# 03-USER_IO_STATUS.net
KiCad netlist of a schematic drawn in Altium Designer
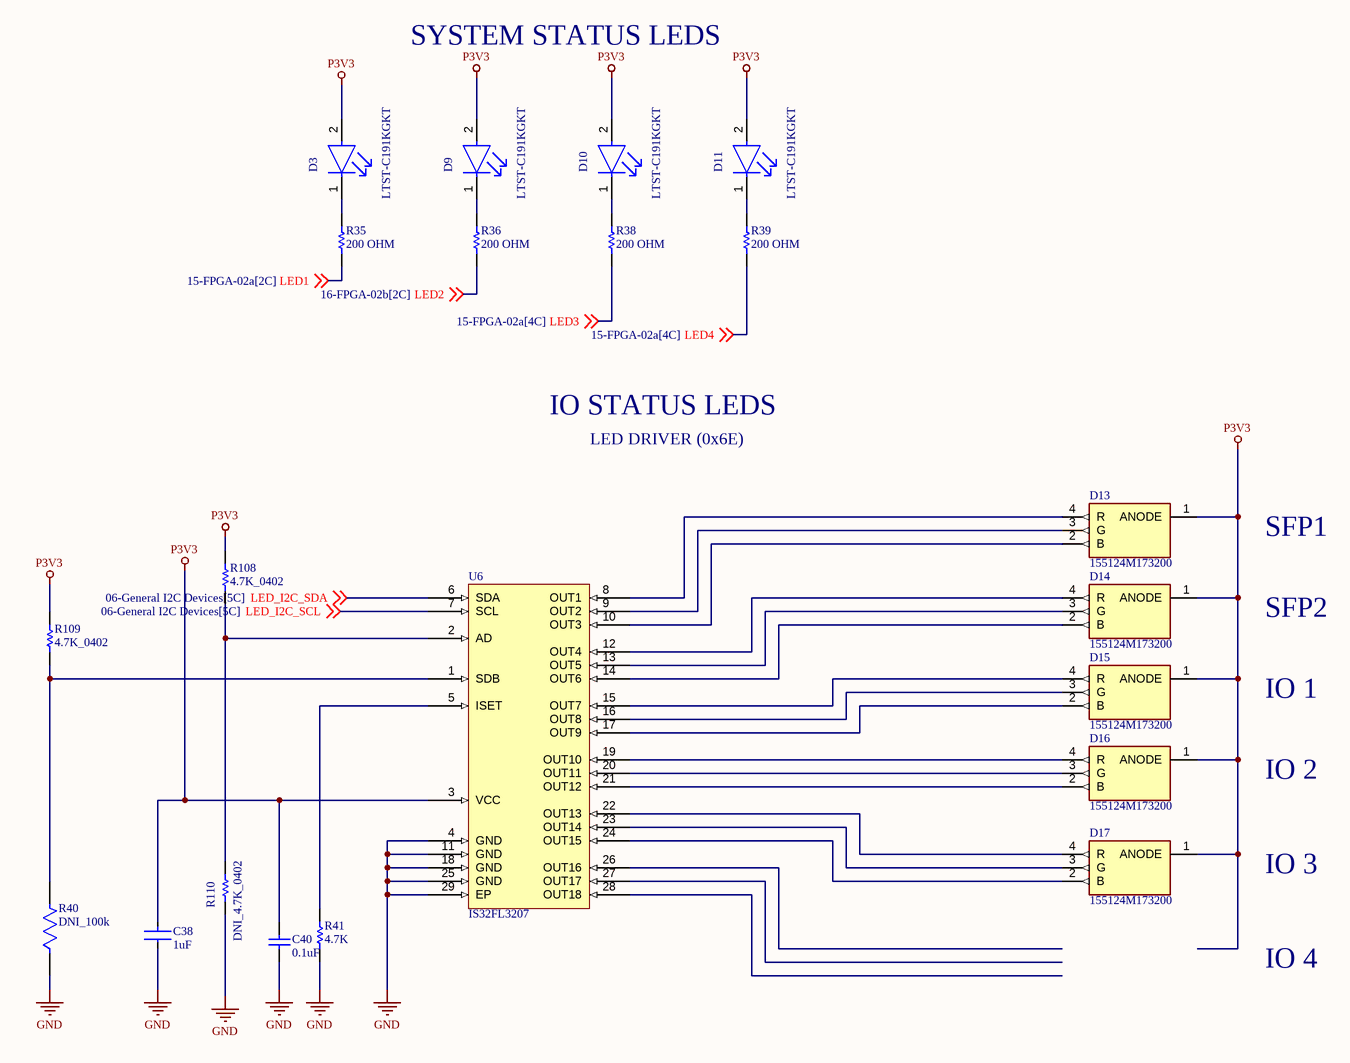
[diagram p0: 03-USER_IO_STATUS.SchDoc]

(export (version "E")
  (design (tool "Eeschema 10.0.6"))
  (components
    (comp (ref "C38")
      (value "1uF")
      (footprint "FP-C0603C105K3PACTU-MFG")
      (description "CAP CER 1UF 25V X5R 0603")
      (fields (field (name "VOLTAGE") "25V") (field (name "TOLERANCE") "10%"))
      (libsource (lib "Altium Content Vault") (part "e9c51b7dd13d4faca003ae77663ab08"))
    )
    (comp (ref "C40")
      (value "0.1uF")
      (footprint "CAPC1608X87X45ML20T05")
      (description "C0603X104K5RACAUTO")
      (fields (field (name "MANUFACTURER") "Kemet"))
      (libsource (lib "Altium Content Vault") (part "CAP"))
    )
    (comp (ref "D3")
      (value "LTST-C191KGKT")
      (footprint "FP-LTST-C191KGKT-MFG")
      (description "LED GREEN CLEAR SMD")
      (libsource (lib "Altium Content Vault") (part "8706943c75ba83719d021d2fdc84c58"))
    )
    (comp (ref "D9")
      (value "LTST-C191KGKT")
      (footprint "FP-LTST-C191KGKT-MFG")
      (description "LED GREEN CLEAR SMD")
      (libsource (lib "Altium Content Vault") (part "8706943c75ba83719d021d2fdc84c58"))
    )
    (comp (ref "D10")
      (value "LTST-C191KGKT")
      (footprint "FP-LTST-C191KGKT-MFG")
      (description "LED GREEN CLEAR SMD")
      (libsource (lib "Altium Content Vault") (part "8706943c75ba83719d021d2fdc84c58"))
    )
    (comp (ref "D11")
      (value "LTST-C191KGKT")
      (footprint "FP-LTST-C191KGKT-MFG")
      (description "LED GREEN CLEAR SMD")
      (libsource (lib "Altium Content Vault") (part "8706943c75ba83719d021d2fdc84c58"))
    )
    (comp (ref "D13")
      (value "155124M173200")
      (footprint "SamacSys:155124M173200")
      (description "LED (Multiple)")
      (fields (field (name "MOUSER PART NUMBER") "710-155124M173200"))
      (libsource (lib "SamacSys") (part "155124M173200"))
    )
    (comp (ref "D14")
      (value "155124M173200")
      (footprint "SamacSys:155124M173200")
      (description "LED (Multiple)")
      (fields (field (name "MOUSER PART NUMBER") "710-155124M173200"))
      (libsource (lib "SamacSys") (part "155124M173200"))
    )
    (comp (ref "D15")
      (value "155124M173200")
      (footprint "SamacSys:155124M173200")
      (description "LED (Multiple)")
      (fields (field (name "MOUSER PART NUMBER") "710-155124M173200"))
      (libsource (lib "SamacSys") (part "155124M173200"))
    )
    (comp (ref "D16")
      (value "155124M173200")
      (footprint "SamacSys:155124M173200")
      (description "LED (Multiple)")
      (fields (field (name "MOUSER PART NUMBER") "710-155124M173200"))
      (libsource (lib "SamacSys") (part "155124M173200"))
    )
    (comp (ref "D17")
      (value "155124M173200")
      (footprint "SamacSys:155124M173200")
      (description "LED (Multiple)")
      (fields (field (name "MOUSER PART NUMBER") "710-155124M173200"))
      (libsource (lib "SamacSys") (part "155124M173200"))
    )
    (comp (ref "R35")
      (value "200 OHM")
      (footprint "RESC1608X55X30NL15T15")
      (description "ERJ-3EKF2000V")
      (fields (field (name "MANUFACTURER") "Panasonic"))
      (libsource (lib "Altium Content Vault") (part "RES"))
    )
    (comp (ref "R36")
      (value "200 OHM")
      (footprint "RESC1608X55X30NL15T15")
      (description "ERJ-3EKF2000V")
      (fields (field (name "MANUFACTURER") "Panasonic"))
      (libsource (lib "Altium Content Vault") (part "RES"))
    )
    (comp (ref "R38")
      (value "200 OHM")
      (footprint "RESC1608X55X30NL15T15")
      (description "ERJ-3EKF2000V")
      (fields (field (name "MANUFACTURER") "Panasonic"))
      (libsource (lib "Altium Content Vault") (part "RES"))
    )
    (comp (ref "R39")
      (value "200 OHM")
      (footprint "RESC1608X55X30NL15T15")
      (description "ERJ-3EKF2000V")
      (fields (field (name "MANUFACTURER") "Panasonic"))
      (libsource (lib "Altium Content Vault") (part "RES"))
    )
    (comp (ref "R40")
      (value "DNI_100k")
      (footprint "FP-RC0603-0_55-MFG")
      (description "RES SMD 100K OHM 1% 1/10W 0603")
      (fields (field (name "TOLERANCE") "1%"))
      (libsource (lib "Altium Content Vault") (part "1029c3af85768c4190bb7ad29bc67b5"))
    )
    (comp (ref "R41")
      (value "4.7K")
      (footprint "RESC1608X55X30NL15T15")
      (fields (field (name "TOLERANCE") "5%"))
      (libsource (lib "Altium Content Vault") (part "RES-2"))
    )
    (comp (ref "R108")
      (value "4.7K_0402")
      (footprint "RESC1005X40X25LL05T05")
      (description "Chip Resistor, 4.7 KOhm, +/- 1%, 0.1 W, -55 to 155 degC, 0402 (1005 Metric), RoHS, Tape and Reel")
      (fields (field (name "TOLERANCE") "1%") (field (name "PARTNUMBER") "ERJ-2RKF4701X"))
      (libsource (lib "Altium Content Vault") (part "RES-2"))
    )
    (comp (ref "R109")
      (value "4.7K_0402")
      (footprint "RESC1005X40X25LL05T05")
      (description "Chip Resistor, 4.7 KOhm, +/- 1%, 0.1 W, -55 to 155 degC, 0402 (1005 Metric), RoHS, Tape and Reel")
      (fields (field (name "TOLERANCE") "1%") (field (name "PARTNUMBER") "ERJ-2RKF4701X"))
      (libsource (lib "Altium Content Vault") (part "RES-2"))
    )
    (comp (ref "R110")
      (value "DNI_4.7K_0402")
      (footprint "RESC1005X40X25LL05T05")
      (description "Chip Resistor, 4.7 KOhm, +/- 1%, 0.1 W, -55 to 155 degC, 0402 (1005 Metric), RoHS, Tape and Reel")
      (fields (field (name "TOLERANCE") "1%") (field (name "PARTNUMBER") "ERJ-2RKF4701X"))
      (libsource (lib "Altium Content Vault") (part "RES-2"))
    )
    (comp (ref "U6")
      (value "IS32FL3207")
      (footprint "IS32FL3207")
      (libsource (lib "IS32FL3207") (part "IS32FL3207"))
    )
  )
  (nets
    (net (code "1") (name "GND") (class "Default")
      (node (ref "C38") (pin "2") (pinfunction "2_2") (pintype "passive"))
      (node (ref "C40") (pin "1") (pinfunction "1_1") (pintype "passive"))
      (node (ref "R110") (pin "2") (pinfunction "2_2") (pintype "passive"))
      (node (ref "R40") (pin "1") (pinfunction "1_1") (pintype "passive"))
      (node (ref "R41") (pin "1") (pinfunction "1_1") (pintype "passive"))
      (node (ref "U6") (pin "11") (pinfunction "GND_11") (pintype "input"))
      (node (ref "U6") (pin "18") (pinfunction "GND_18") (pintype "input"))
      (node (ref "U6") (pin "25") (pinfunction "GND_25") (pintype "input"))
      (node (ref "U6") (pin "29") (pinfunction "EP_29") (pintype "input"))
      (node (ref "U6") (pin "4") (pinfunction "GND_4") (pintype "input"))
    )
    (net (code "2") (name "LED1") (class "Default")
      (node (ref "R35") (pin "1") (pinfunction "1_1") (pintype "passive"))
    )
    (net (code "3") (name "LED2") (class "Default")
      (node (ref "R36") (pin "1") (pinfunction "1_1") (pintype "passive"))
    )
    (net (code "4") (name "LED3") (class "Default")
      (node (ref "R38") (pin "1") (pinfunction "1_1") (pintype "passive"))
    )
    (net (code "5") (name "LED4") (class "Default")
      (node (ref "R39") (pin "1") (pinfunction "1_1") (pintype "passive"))
    )
    (net (code "6") (name "LED_I2C_SCL") (class "Default")
      (node (ref "U6") (pin "7") (pinfunction "SCL_7") (pintype "input"))
    )
    (net (code "7") (name "LED_I2C_SDA") (class "Default")
      (node (ref "U6") (pin "6") (pinfunction "SDA_6") (pintype "input"))
    )
    (net (code "8") (name "Net-(D3-C)") (class "Default")
      (node (ref "D3") (pin "1") (pinfunction "C_1") (pintype "passive"))
      (node (ref "R35") (pin "2") (pinfunction "2_2") (pintype "passive"))
    )
    (net (code "9") (name "Net-(D9-C)") (class "Default")
      (node (ref "D9") (pin "1") (pinfunction "C_1") (pintype "passive"))
      (node (ref "R36") (pin "2") (pinfunction "2_2") (pintype "passive"))
    )
    (net (code "10") (name "Net-(D10-C)") (class "Default")
      (node (ref "D10") (pin "1") (pinfunction "C_1") (pintype "passive"))
      (node (ref "R38") (pin "2") (pinfunction "2_2") (pintype "passive"))
    )
    (net (code "11") (name "Net-(D11-C)") (class "Default")
      (node (ref "D11") (pin "1") (pinfunction "C_1") (pintype "passive"))
      (node (ref "R39") (pin "2") (pinfunction "2_2") (pintype "passive"))
    )
    (net (code "12") (name "Net-(D13-B)") (class "Default")
      (node (ref "D13") (pin "2") (pinfunction "B_2") (pintype "output"))
      (node (ref "U6") (pin "10") (pinfunction "OUT3_10") (pintype "input"))
    )
    (net (code "13") (name "Net-(D13-G)") (class "Default")
      (node (ref "D13") (pin "3") (pinfunction "G_3") (pintype "output"))
      (node (ref "U6") (pin "9") (pinfunction "OUT2_9") (pintype "input"))
    )
    (net (code "14") (name "Net-(D13-R)") (class "Default")
      (node (ref "D13") (pin "4") (pinfunction "R_4") (pintype "output"))
      (node (ref "U6") (pin "8") (pinfunction "OUT1_8") (pintype "input"))
    )
    (net (code "15") (name "Net-(D14-B)") (class "Default")
      (node (ref "D14") (pin "2") (pinfunction "B_2") (pintype "output"))
      (node (ref "U6") (pin "14") (pinfunction "OUT6_14") (pintype "input"))
    )
    (net (code "16") (name "Net-(D14-G)") (class "Default")
      (node (ref "D14") (pin "3") (pinfunction "G_3") (pintype "output"))
      (node (ref "U6") (pin "13") (pinfunction "OUT5_13") (pintype "input"))
    )
    (net (code "17") (name "Net-(D14-R)") (class "Default")
      (node (ref "D14") (pin "4") (pinfunction "R_4") (pintype "output"))
      (node (ref "U6") (pin "12") (pinfunction "OUT4_12") (pintype "input"))
    )
    (net (code "18") (name "Net-(D15-B)") (class "Default")
      (node (ref "D15") (pin "2") (pinfunction "B_2") (pintype "output"))
      (node (ref "U6") (pin "17") (pinfunction "OUT9_17") (pintype "input"))
    )
    (net (code "19") (name "Net-(D15-G)") (class "Default")
      (node (ref "D15") (pin "3") (pinfunction "G_3") (pintype "output"))
      (node (ref "U6") (pin "16") (pinfunction "OUT8_16") (pintype "input"))
    )
    (net (code "20") (name "Net-(D15-R)") (class "Default")
      (node (ref "D15") (pin "4") (pinfunction "R_4") (pintype "output"))
      (node (ref "U6") (pin "15") (pinfunction "OUT7_15") (pintype "input"))
    )
    (net (code "21") (name "Net-(D16-B)") (class "Default")
      (node (ref "D16") (pin "2") (pinfunction "B_2") (pintype "output"))
      (node (ref "U6") (pin "21") (pinfunction "OUT12_21") (pintype "input"))
    )
    (net (code "22") (name "Net-(D16-G)") (class "Default")
      (node (ref "D16") (pin "3") (pinfunction "G_3") (pintype "output"))
      (node (ref "U6") (pin "20") (pinfunction "OUT11_20") (pintype "input"))
    )
    (net (code "23") (name "Net-(D16-R)") (class "Default")
      (node (ref "D16") (pin "4") (pinfunction "R_4") (pintype "output"))
      (node (ref "U6") (pin "19") (pinfunction "OUT10_19") (pintype "input"))
    )
    (net (code "24") (name "Net-(D17-B)") (class "Default")
      (node (ref "D17") (pin "2") (pinfunction "B_2") (pintype "output"))
      (node (ref "U6") (pin "24") (pinfunction "OUT15_24") (pintype "input"))
    )
    (net (code "25") (name "Net-(D17-G)") (class "Default")
      (node (ref "D17") (pin "3") (pinfunction "G_3") (pintype "output"))
      (node (ref "U6") (pin "23") (pinfunction "OUT14_23") (pintype "input"))
    )
    (net (code "26") (name "Net-(D17-R)") (class "Default")
      (node (ref "D17") (pin "4") (pinfunction "R_4") (pintype "output"))
      (node (ref "U6") (pin "22") (pinfunction "OUT13_22") (pintype "input"))
    )
    (net (code "27") (name "Net-(U6-AD)") (class "Default")
      (node (ref "R108") (pin "2") (pinfunction "2_2") (pintype "passive"))
      (node (ref "R110") (pin "1") (pinfunction "1_1") (pintype "passive"))
      (node (ref "U6") (pin "2") (pinfunction "AD_2") (pintype "input"))
    )
    (net (code "28") (name "Net-(U6-ISET)") (class "Default")
      (node (ref "R41") (pin "2") (pinfunction "2_2") (pintype "passive"))
      (node (ref "U6") (pin "5") (pinfunction "ISET_5") (pintype "input"))
    )
    (net (code "29") (name "Net-(U6-SDB)") (class "Default")
      (node (ref "R109") (pin "2") (pinfunction "2_2") (pintype "passive"))
      (node (ref "R40") (pin "2") (pinfunction "2_2") (pintype "passive"))
      (node (ref "U6") (pin "1") (pinfunction "SDB_1") (pintype "input"))
    )
    (net (code "30") (name "P3V3") (class "Default")
      (node (ref "C38") (pin "1") (pinfunction "1_1") (pintype "passive"))
      (node (ref "C40") (pin "2") (pinfunction "2_2") (pintype "passive"))
      (node (ref "D10") (pin "2") (pinfunction "A_2") (pintype "passive"))
      (node (ref "D11") (pin "2") (pinfunction "A_2") (pintype "passive"))
      (node (ref "D13") (pin "1") (pinfunction "ANODE_1") (pintype "power_in"))
      (node (ref "D14") (pin "1") (pinfunction "ANODE_1") (pintype "power_in"))
      (node (ref "D15") (pin "1") (pinfunction "ANODE_1") (pintype "power_in"))
      (node (ref "D16") (pin "1") (pinfunction "ANODE_1") (pintype "power_in"))
      (node (ref "D17") (pin "1") (pinfunction "ANODE_1") (pintype "power_in"))
      (node (ref "D3") (pin "2") (pinfunction "A_2") (pintype "passive"))
      (node (ref "D9") (pin "2") (pinfunction "A_2") (pintype "passive"))
      (node (ref "R108") (pin "1") (pinfunction "1_1") (pintype "passive"))
      (node (ref "R109") (pin "1") (pinfunction "1_1") (pintype "passive"))
      (node (ref "U6") (pin "3") (pinfunction "VCC_3") (pintype "input"))
    )
    (net (code "31") (name "unconnected-(U6-OUT16-Pad26)") (class "Default")
      (node (ref "U6") (pin "26") (pinfunction "OUT16_26") (pintype "input"))
    )
    (net (code "32") (name "unconnected-(U6-OUT17-Pad27)") (class "Default")
      (node (ref "U6") (pin "27") (pinfunction "OUT17_27") (pintype "input"))
    )
    (net (code "33") (name "unconnected-(U6-OUT18-Pad28)") (class "Default")
      (node (ref "U6") (pin "28") (pinfunction "OUT18_28") (pintype "input"))
    )
  )
)
